# stm32f103c8.net
KiCad netlist of a schematic drawn in Altium Designer
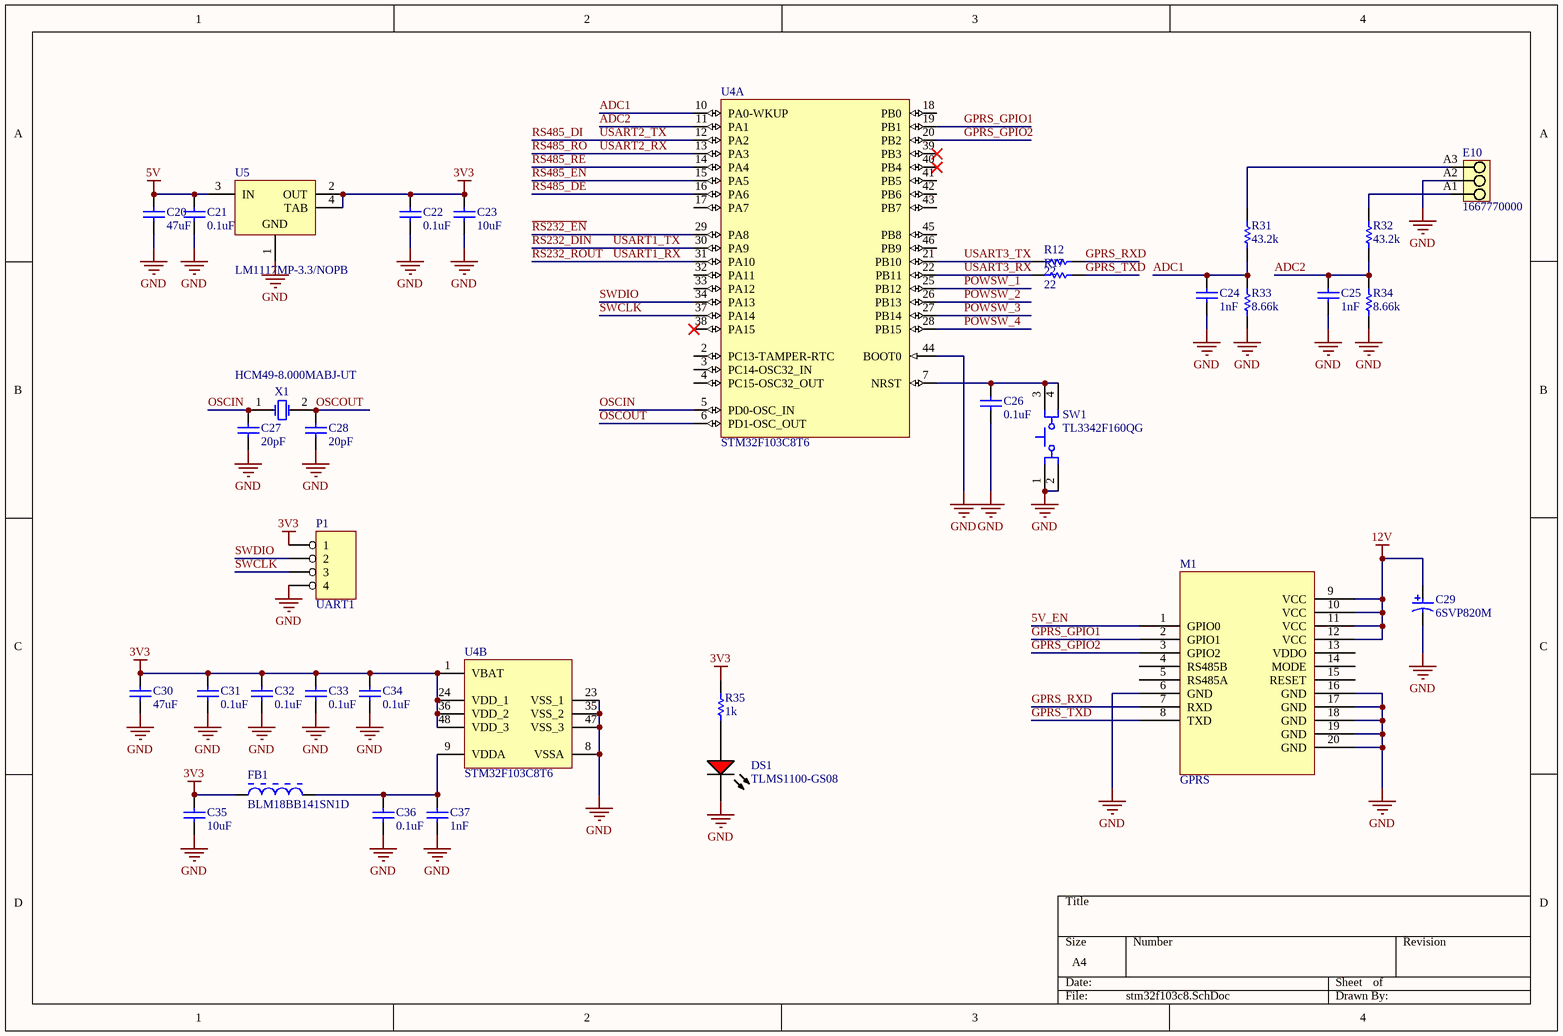
[diagram p0: stm32f103c8.SchDoc]

(export (version "E")
  (design (tool "Eeschema 10.0.6"))
  (components
    (comp (ref "C20")
      (value "47uF")
      (footprint "CAPC1206(3216)150_L")
      (description "1206 (3216 Metric) Chip Capacitor")
      (libsource (lib "IC0") (part "CAP_5_3"))
    )
    (comp (ref "C21")
      (value "0.1uF")
      (footprint "CAPC0603(1608)100_L")
      (description "0603 (1608 Metric) Chip Capacitor")
      (libsource (lib "IC0") (part "CAP_5"))
    )
    (comp (ref "C22")
      (value "0.1uF")
      (footprint "CAPC0603(1608)100_L")
      (description "0603 (1608 Metric) Chip Capacitor")
      (libsource (lib "IC0") (part "CAP_5"))
    )
    (comp (ref "C23")
      (value "10uF")
      (footprint "CAPC0805(2012)145_L")
      (description "0805 (2012 Metric) Chip Capacitor")
      (libsource (lib "IC0") (part "CAP_5_1"))
    )
    (comp (ref "C24")
      (value "1nF")
      (footprint "CAPC0603(1608)100_L")
      (description "0603 (1608 Metric) Chip Capacitor")
      (libsource (lib "IC0") (part "CAP_5"))
    )
    (comp (ref "C25")
      (value "1nF")
      (footprint "CAPC0603(1608)100_L")
      (description "0603 (1608 Metric) Chip Capacitor")
      (libsource (lib "IC0") (part "CAP_5"))
    )
    (comp (ref "C26")
      (value "0.1uF")
      (footprint "CAPC0603(1608)100_L")
      (description "0603 (1608 Metric) Chip Capacitor")
      (libsource (lib "IC0") (part "CAP_5"))
    )
    (comp (ref "C27")
      (value "20pF")
      (footprint "CAPC0603(1608)100_L")
      (description "0603 (1608 Metric) Chip Capacitor")
      (libsource (lib "IC0") (part "CAP_5"))
    )
    (comp (ref "C28")
      (value "20pF")
      (footprint "CAPC0603(1608)100_L")
      (description "0603 (1608 Metric) Chip Capacitor")
      (libsource (lib "IC0") (part "CAP_5"))
    )
    (comp (ref "C29")
      (value "6SVP820M")
      (footprint "PNSC-SVP-F12_L")
      (fields (field (name "TOLERANCE") "±20%") (field (name "MANUFACTURER") "Panasonic"))
      (libsource (lib "Altium Content Vault") (part "CAP-P-2"))
    )
    (comp (ref "C30")
      (value "47uF")
      (footprint "CAPC1206(3216)150_L")
      (description "1206 (3216 Metric) Chip Capacitor")
      (libsource (lib "IC0") (part "CAP_5_3"))
    )
    (comp (ref "C31")
      (value "0.1uF")
      (footprint "CAPC0603(1608)100_L")
      (description "0603 (1608 Metric) Chip Capacitor")
      (libsource (lib "IC0") (part "CAP_5"))
    )
    (comp (ref "C32")
      (value "0.1uF")
      (footprint "CAPC0603(1608)100_L")
      (description "0603 (1608 Metric) Chip Capacitor")
      (libsource (lib "IC0") (part "CAP_5"))
    )
    (comp (ref "C33")
      (value "0.1uF")
      (footprint "CAPC0603(1608)100_L")
      (description "0603 (1608 Metric) Chip Capacitor")
      (libsource (lib "IC0") (part "CAP_5"))
    )
    (comp (ref "C34")
      (value "0.1uF")
      (footprint "CAPC0603(1608)100_L")
      (description "0603 (1608 Metric) Chip Capacitor")
      (libsource (lib "IC0") (part "CAP_5"))
    )
    (comp (ref "C35")
      (value "10uF")
      (footprint "CAPC0603(1608)100_L")
      (description "0603 (1608 Metric) Chip Capacitor")
      (libsource (lib "IC0") (part "CAP_5"))
    )
    (comp (ref "C36")
      (value "0.1uF")
      (footprint "CAPC0603(1608)100_L")
      (description "0603 (1608 Metric) Chip Capacitor")
      (libsource (lib "IC0") (part "CAP_5"))
    )
    (comp (ref "C37")
      (value "1nF")
      (footprint "CAPC0603(1608)100_L")
      (description "0603 (1608 Metric) Chip Capacitor")
      (libsource (lib "IC0") (part "CAP_5"))
    )
    (comp (ref "DS1")
      (value "TLMS1100-GS08")
      (footprint "VISH-TLMX1100_V")
      (description "LED, RED, 2.1 V, -40 to 100 degC, 2-Pin SMD (0603), RoHS, Tape and Reel")
      (fields (field (name "TOLERANCE") "5%"))
      (libsource (lib "Altium Content Vault") (part "LED-RED-AK-2"))
    )
    (comp (ref "E10")
      (value "1667770000")
      (footprint "LM_3_5_90_03")
      (description "OMNIMATE Signal - series LM")
      (fields (field (name "MANUFACTURER") "Weidmueller"))
      (libsource (lib "Altium Content Vault") (part "Terminal_03_1x03"))
    )
    (comp (ref "FB1")
      (value "BLM18BB141SN1D")
      (footprint "MURA-BLM18-RF-H4-CHIP-2_V")
      (fields (field (name "MANUFACTURER") "Murata"))
      (libsource (lib "IC0") (part "MURA-FB-2"))
    )
    (comp (ref "M1") (value "GPRS") (footprint "GPRS") (libsource (lib "gprs") (part "GPRS_M")))
    (comp (ref "P1") (value "UART1") (footprint "header4") (libsource (lib "IC0") (part "HEADER 4")))
    (comp (ref "R12")
      (value "22")
      (footprint "RESC0603(1608)_L")
      (description "0603 (1608 Metric) Chip Resistor")
      (libsource (lib "PCB_Project1") (part "RES_3_1"))
    )
    (comp (ref "R17")
      (value "22")
      (footprint "RESC0603(1608)_L")
      (description "0603 (1608 Metric) Chip Resistor")
      (libsource (lib "PCB_Project1") (part "RES_3_1"))
    )
    (comp (ref "R31")
      (value "43.2k")
      (footprint "RESC0603(1608)_L")
      (description "0603 (1608 Metric) Chip Resistor")
      (libsource (lib "PCB_Project1") (part "RES_3_1"))
    )
    (comp (ref "R32")
      (value "43.2k")
      (footprint "RESC0603(1608)_L")
      (description "0603 (1608 Metric) Chip Resistor")
      (libsource (lib "PCB_Project1") (part "RES_3_1"))
    )
    (comp (ref "R33")
      (value "8.66k")
      (footprint "RESC0603(1608)_L")
      (description "0603 (1608 Metric) Chip Resistor")
      (libsource (lib "PCB_Project1") (part "RES_3_1"))
    )
    (comp (ref "R34")
      (value "8.66k")
      (footprint "RESC0603(1608)_L")
      (description "0603 (1608 Metric) Chip Resistor")
      (libsource (lib "PCB_Project1") (part "RES_3_1"))
    )
    (comp (ref "R35")
      (value "1k")
      (footprint "RESC0603(1608)_L")
      (description "0603 (1608 Metric) Chip Resistor")
      (libsource (lib "PCB_Project1") (part "RES_3_1"))
    )
    (comp (ref "SW1")
      (value "TL3342F160QG")
      (footprint "ESWI-TL3342F160QG_V")
      (description "Switch, Tactile, SPST-NO, 50 mA, 12 V, 4-Pin SMD, RoHS, Tape and Reel")
      (fields (field (name "TOLERANCE") "20%"))
      (libsource (lib "Altium Content Vault") (part "SW-SPST-NO-4"))
    )
    (comp (ref "U4")
      (value "STM32F103C8T6")
      (footprint "STM-LQFP48_L")
      (libsource (lib "Altium Content Vault") (part "MC-ARM-STM32F103X8_B-SQ48"))
    )
    (comp (ref "U5")
      (value "LM1117MP-3.3/NOPB")
      (footprint "DCY0004A_L")
      (description "800mA Low-Dropout Linear Regulator, 4-pin SOT-223, Pb-Free")
      (fields (field (name "MANUFACTURER") "Texas Instruments"))
      (libsource (lib "Altium Content Vault") (part "PM-REG-LM1086-SOT4"))
    )
    (comp (ref "X1")
      (value "HCM49-8.000MABJ-UT")
      (footprint "CFM-HCM49-2_V")
      (description "At-Cut Crystal Unit, 3.5 to 30 MHz, -40 to 85 degC, 2-Pin 11.4Ã—4.7Ã—4.3 mm SMD, RoHS, Reel")
      (fields (field (name "MANUFACTURER") "Citizen Finetech Miyota"))
      (libsource (lib "Altium Content Vault") (part "CFM-HCM49-2"))
    )
  )
  (nets
    (net (code "1") (name "/5V_EN") (class "Default")
      (node (ref "M1") (pin "1") (pinfunction "GPIO0_1") (pintype "passive"))
    )
    (net (code "2") (name "/ADC1") (class "Default")
      (node (ref "C24") (pin "2") (pinfunction "2_2") (pintype "passive"))
      (node (ref "R31") (pin "1") (pinfunction "1_1") (pintype "passive"))
      (node (ref "R33") (pin "2") (pinfunction "2_2") (pintype "passive"))
      (node (ref "U4") (pin "10") (pinfunction "PA0-WKUP_10") (pintype "bidirectional"))
    )
    (net (code "3") (name "/ADC2") (class "Default")
      (node (ref "C25") (pin "2") (pinfunction "2_2") (pintype "passive"))
      (node (ref "R32") (pin "1") (pinfunction "1_1") (pintype "passive"))
      (node (ref "R34") (pin "2") (pinfunction "2_2") (pintype "passive"))
      (node (ref "U4") (pin "11") (pinfunction "PA1_11") (pintype "bidirectional"))
    )
    (net (code "4") (name "/GPRS_GPIO1") (class "Default")
      (node (ref "M1") (pin "2") (pinfunction "GPIO1_2") (pintype "passive"))
      (node (ref "U4") (pin "19") (pinfunction "PB1_19") (pintype "bidirectional"))
    )
    (net (code "5") (name "/GPRS_GPIO2") (class "Default")
      (node (ref "M1") (pin "3") (pinfunction "GPIO2_3") (pintype "passive"))
      (node (ref "U4") (pin "20") (pinfunction "PB2_20") (pintype "bidirectional"))
    )
    (net (code "6") (name "/GPRS_RXD") (class "Default")
      (node (ref "M1") (pin "7") (pinfunction "RXD_7") (pintype "passive"))
      (node (ref "R12") (pin "1") (pinfunction "1_1") (pintype "passive"))
    )
    (net (code "7") (name "/GPRS_TXD") (class "Default")
      (node (ref "M1") (pin "8") (pinfunction "TXD_8") (pintype "passive"))
      (node (ref "R17") (pin "1") (pinfunction "1_1") (pintype "passive"))
    )
    (net (code "8") (name "/OSCIN") (class "Default")
      (node (ref "C27") (pin "2") (pinfunction "2_2") (pintype "passive"))
      (node (ref "U4") (pin "5") (pinfunction "PD0-OSC_IN_5") (pintype "bidirectional"))
      (node (ref "X1") (pin "1") (pinfunction "X1_1") (pintype "passive"))
    )
    (net (code "9") (name "/OSCOUT") (class "Default")
      (node (ref "C28") (pin "2") (pinfunction "2_2") (pintype "passive"))
      (node (ref "U4") (pin "6") (pinfunction "PD1-OSC_OUT_6") (pintype "bidirectional"))
      (node (ref "X1") (pin "2") (pinfunction "X2_2") (pintype "passive"))
    )
    (net (code "10") (name "/POWSW_1") (class "Default")
      (node (ref "U4") (pin "25") (pinfunction "PB12_25") (pintype "bidirectional"))
    )
    (net (code "11") (name "/POWSW_2") (class "Default")
      (node (ref "U4") (pin "26") (pinfunction "PB13_26") (pintype "bidirectional"))
    )
    (net (code "12") (name "/POWSW_3") (class "Default")
      (node (ref "U4") (pin "27") (pinfunction "PB14_27") (pintype "bidirectional"))
    )
    (net (code "13") (name "/POWSW_4") (class "Default")
      (node (ref "U4") (pin "28") (pinfunction "PB15_28") (pintype "bidirectional"))
    )
    (net (code "14") (name "/RS232_DIN") (class "Default")
      (node (ref "U4") (pin "30") (pinfunction "PA9_30") (pintype "bidirectional"))
    )
    (net (code "15") (name "/RS232_ROUT") (class "Default")
      (node (ref "U4") (pin "31") (pinfunction "PA10_31") (pintype "bidirectional"))
    )
    (net (code "16") (name "/RS485_DE") (class "Default")
      (node (ref "U4") (pin "16") (pinfunction "PA6_16") (pintype "bidirectional"))
    )
    (net (code "17") (name "/RS485_DI") (class "Default")
      (node (ref "U4") (pin "12") (pinfunction "PA2_12") (pintype "bidirectional"))
    )
    (net (code "18") (name "/RS485_RO") (class "Default")
      (node (ref "U4") (pin "13") (pinfunction "PA3_13") (pintype "bidirectional"))
    )
    (net (code "19") (name "/RS485_~{RE}") (class "Default")
      (node (ref "U4") (pin "14") (pinfunction "PA4_14") (pintype "bidirectional"))
    )
    (net (code "20") (name "/SWCLK") (class "Default")
      (node (ref "P1") (pin "3") (pinfunction "3_3") (pintype "passive"))
      (node (ref "U4") (pin "37") (pinfunction "PA14_37") (pintype "bidirectional"))
    )
    (net (code "21") (name "/SWDIO") (class "Default")
      (node (ref "P1") (pin "2") (pinfunction "2_2") (pintype "passive"))
      (node (ref "U4") (pin "34") (pinfunction "PA13_34") (pintype "bidirectional"))
    )
    (net (code "22") (name "/USART3_RX") (class "Default")
      (node (ref "R17") (pin "2") (pinfunction "2_2") (pintype "passive"))
      (node (ref "U4") (pin "22") (pinfunction "PB11_22") (pintype "bidirectional"))
    )
    (net (code "23") (name "/USART3_TX") (class "Default")
      (node (ref "R12") (pin "2") (pinfunction "2_2") (pintype "passive"))
      (node (ref "U4") (pin "21") (pinfunction "PB10_21") (pintype "bidirectional"))
    )
    (net (code "24") (name "/~{RS232_EN}") (class "Default")
      (node (ref "U4") (pin "29") (pinfunction "PA8_29") (pintype "bidirectional"))
    )
    (net (code "25") (name "/~{RS485_EN}") (class "Default")
      (node (ref "U4") (pin "15") (pinfunction "PA5_15") (pintype "bidirectional"))
    )
    (net (code "26") (name "3V3") (class "Default")
      (node (ref "C22") (pin "2") (pinfunction "2_2") (pintype "passive"))
      (node (ref "C23") (pin "2") (pinfunction "2_2") (pintype "passive"))
      (node (ref "C30") (pin "2") (pinfunction "2_2") (pintype "passive"))
      (node (ref "C31") (pin "2") (pinfunction "2_2") (pintype "passive"))
      (node (ref "C32") (pin "2") (pinfunction "2_2") (pintype "passive"))
      (node (ref "C33") (pin "2") (pinfunction "2_2") (pintype "passive"))
      (node (ref "C34") (pin "2") (pinfunction "2_2") (pintype "passive"))
      (node (ref "C35") (pin "2") (pinfunction "2_2") (pintype "passive"))
      (node (ref "FB1") (pin "1") (pinfunction "1_1") (pintype "passive"))
      (node (ref "P1") (pin "1") (pinfunction "1_1") (pintype "passive"))
      (node (ref "R35") (pin "2") (pinfunction "2_2") (pintype "passive"))
      (node (ref "U4") (pin "1") (pinfunction "VBAT_1") (pintype "power_in"))
      (node (ref "U4") (pin "24") (pinfunction "VDD_1_24") (pintype "power_in"))
      (node (ref "U4") (pin "36") (pinfunction "VDD_2_36") (pintype "power_in"))
      (node (ref "U4") (pin "48") (pinfunction "VDD_3_48") (pintype "power_in"))
      (node (ref "U5") (pin "2") (pinfunction "OUT_2") (pintype "power_in"))
      (node (ref "U5") (pin "4") (pinfunction "TAB_4") (pintype "power_in"))
    )
    (net (code "27") (name "5V") (class "Default")
      (node (ref "C20") (pin "2") (pinfunction "2_2") (pintype "passive"))
      (node (ref "C21") (pin "2") (pinfunction "2_2") (pintype "passive"))
      (node (ref "U5") (pin "3") (pinfunction "IN_3") (pintype "power_in"))
    )
    (net (code "28") (name "12V") (class "Default")
      (node (ref "C29") (pin "1") (pinfunction "1_1") (pintype "passive"))
      (node (ref "M1") (pin "10") (pinfunction "VCC_10") (pintype "passive"))
      (node (ref "M1") (pin "11") (pinfunction "VCC_11") (pintype "passive"))
      (node (ref "M1") (pin "12") (pinfunction "VCC_12") (pintype "passive"))
      (node (ref "M1") (pin "9") (pinfunction "VCC_9") (pintype "passive"))
    )
    (net (code "29") (name "GND") (class "Default")
      (node (ref "C20") (pin "1") (pinfunction "1_1") (pintype "passive"))
      (node (ref "C21") (pin "1") (pinfunction "1_1") (pintype "passive"))
      (node (ref "C22") (pin "1") (pinfunction "1_1") (pintype "passive"))
      (node (ref "C23") (pin "1") (pinfunction "1_1") (pintype "passive"))
      (node (ref "C24") (pin "1") (pinfunction "1_1") (pintype "passive"))
      (node (ref "C25") (pin "1") (pinfunction "1_1") (pintype "passive"))
      (node (ref "C26") (pin "1") (pinfunction "1_1") (pintype "passive"))
      (node (ref "C27") (pin "1") (pinfunction "1_1") (pintype "passive"))
      (node (ref "C28") (pin "1") (pinfunction "1_1") (pintype "passive"))
      (node (ref "C29") (pin "2") (pinfunction "2_2") (pintype "passive"))
      (node (ref "C30") (pin "1") (pinfunction "1_1") (pintype "passive"))
      (node (ref "C31") (pin "1") (pinfunction "1_1") (pintype "passive"))
      (node (ref "C32") (pin "1") (pinfunction "1_1") (pintype "passive"))
      (node (ref "C33") (pin "1") (pinfunction "1_1") (pintype "passive"))
      (node (ref "C34") (pin "1") (pinfunction "1_1") (pintype "passive"))
      (node (ref "C35") (pin "1") (pinfunction "1_1") (pintype "passive"))
      (node (ref "C36") (pin "1") (pinfunction "1_1") (pintype "passive"))
      (node (ref "C37") (pin "1") (pinfunction "1_1") (pintype "passive"))
      (node (ref "DS1") (pin "2") (pinfunction "K_2") (pintype "passive"))
      (node (ref "E10") (pin "A2") (pinfunction "A2_A2") (pintype "passive"))
      (node (ref "M1") (pin "16") (pinfunction "GND_16") (pintype "passive"))
      (node (ref "M1") (pin "17") (pinfunction "GND_17") (pintype "passive"))
      (node (ref "M1") (pin "18") (pinfunction "GND_18") (pintype "passive"))
      (node (ref "M1") (pin "19") (pinfunction "GND_19") (pintype "passive"))
      (node (ref "M1") (pin "20") (pinfunction "GND_20") (pintype "passive"))
      (node (ref "M1") (pin "6") (pinfunction "GND_6") (pintype "passive"))
      (node (ref "P1") (pin "4") (pinfunction "4_4") (pintype "passive"))
      (node (ref "R33") (pin "1") (pinfunction "1_1") (pintype "passive"))
      (node (ref "R34") (pin "1") (pinfunction "1_1") (pintype "passive"))
      (node (ref "SW1") (pin "1") (pinfunction "1_1") (pintype "passive"))
      (node (ref "SW1") (pin "2") (pinfunction "2_2") (pintype "passive"))
      (node (ref "U4") (pin "23") (pinfunction "VSS_1_23") (pintype "power_in"))
      (node (ref "U4") (pin "35") (pinfunction "VSS_2_35") (pintype "power_in"))
      (node (ref "U4") (pin "44") (pinfunction "BOOT0_44") (pintype "input"))
      (node (ref "U4") (pin "47") (pinfunction "VSS_3_47") (pintype "power_in"))
      (node (ref "U4") (pin "8") (pinfunction "VSSA_8") (pintype "power_in"))
      (node (ref "U5") (pin "1") (pinfunction "GND_1") (pintype "power_in"))
    )
    (net (code "30") (name "Net-(DS1-A)") (class "Default")
      (node (ref "DS1") (pin "1") (pinfunction "A_1") (pintype "passive"))
      (node (ref "R35") (pin "1") (pinfunction "1_1") (pintype "passive"))
    )
    (net (code "31") (name "Net-(E10-PadA1)") (class "Default")
      (node (ref "E10") (pin "A1") (pinfunction "A1_A1") (pintype "passive"))
      (node (ref "R32") (pin "2") (pinfunction "2_2") (pintype "passive"))
    )
    (net (code "32") (name "Net-(E10-PadA3)") (class "Default")
      (node (ref "E10") (pin "A3") (pinfunction "A3_A3") (pintype "passive"))
      (node (ref "R31") (pin "2") (pinfunction "2_2") (pintype "passive"))
    )
    (net (code "33") (name "Net-(U4A-NRST)") (class "Default")
      (node (ref "C26") (pin "2") (pinfunction "2_2") (pintype "passive"))
      (node (ref "SW1") (pin "3") (pinfunction "3_3") (pintype "passive"))
      (node (ref "SW1") (pin "4") (pinfunction "4_4") (pintype "passive"))
      (node (ref "U4") (pin "7") (pinfunction "NRST_7") (pintype "bidirectional"))
    )
    (net (code "34") (name "Net-(U4B-VDDA)") (class "Default")
      (node (ref "C36") (pin "2") (pinfunction "2_2") (pintype "passive"))
      (node (ref "C37") (pin "2") (pinfunction "2_2") (pintype "passive"))
      (node (ref "FB1") (pin "2") (pinfunction "2_2") (pintype "passive"))
      (node (ref "U4") (pin "9") (pinfunction "VDDA_9") (pintype "power_in"))
    )
    (net (code "35") (name "unconnected-(M1-MODE-Pad14)") (class "Default")
      (node (ref "M1") (pin "14") (pinfunction "MODE_14") (pintype "passive"))
    )
    (net (code "36") (name "unconnected-(M1-RESET-Pad15)") (class "Default")
      (node (ref "M1") (pin "15") (pinfunction "RESET_15") (pintype "passive"))
    )
    (net (code "37") (name "unconnected-(M1-RS485A-Pad5)") (class "Default")
      (node (ref "M1") (pin "5") (pinfunction "RS485A_5") (pintype "passive"))
    )
    (net (code "38") (name "unconnected-(M1-RS485B-Pad4)") (class "Default")
      (node (ref "M1") (pin "4") (pinfunction "RS485B_4") (pintype "passive"))
    )
    (net (code "39") (name "unconnected-(M1-VDDO-Pad13)") (class "Default")
      (node (ref "M1") (pin "13") (pinfunction "VDDO_13") (pintype "passive"))
    )
    (net (code "40") (name "unconnected-(U4A-PA7-Pad17)") (class "Default")
      (node (ref "U4") (pin "17") (pinfunction "PA7_17") (pintype "bidirectional"))
    )
    (net (code "41") (name "unconnected-(U4A-PA11-Pad32)") (class "Default")
      (node (ref "U4") (pin "32") (pinfunction "PA11_32") (pintype "bidirectional"))
    )
    (net (code "42") (name "unconnected-(U4A-PA12-Pad33)") (class "Default")
      (node (ref "U4") (pin "33") (pinfunction "PA12_33") (pintype "bidirectional"))
    )
    (net (code "43") (name "unconnected-(U4A-PA15-Pad38)") (class "Default")
      (node (ref "U4") (pin "38") (pinfunction "PA15_38") (pintype "bidirectional+no_connect"))
    )
    (net (code "44") (name "unconnected-(U4A-PB0-Pad18)") (class "Default")
      (node (ref "U4") (pin "18") (pinfunction "PB0_18") (pintype "bidirectional"))
    )
    (net (code "45") (name "unconnected-(U4A-PB3-Pad39)") (class "Default")
      (node (ref "U4") (pin "39") (pinfunction "PB3_39") (pintype "bidirectional+no_connect"))
    )
    (net (code "46") (name "unconnected-(U4A-PB4-Pad40)") (class "Default")
      (node (ref "U4") (pin "40") (pinfunction "PB4_40") (pintype "bidirectional+no_connect"))
    )
    (net (code "47") (name "unconnected-(U4A-PB5-Pad41)") (class "Default")
      (node (ref "U4") (pin "41") (pinfunction "PB5_41") (pintype "bidirectional"))
    )
    (net (code "48") (name "unconnected-(U4A-PB6-Pad42)") (class "Default")
      (node (ref "U4") (pin "42") (pinfunction "PB6_42") (pintype "bidirectional"))
    )
    (net (code "49") (name "unconnected-(U4A-PB7-Pad43)") (class "Default")
      (node (ref "U4") (pin "43") (pinfunction "PB7_43") (pintype "bidirectional"))
    )
    (net (code "50") (name "unconnected-(U4A-PB8-Pad45)") (class "Default")
      (node (ref "U4") (pin "45") (pinfunction "PB8_45") (pintype "bidirectional"))
    )
    (net (code "51") (name "unconnected-(U4A-PB9-Pad46)") (class "Default")
      (node (ref "U4") (pin "46") (pinfunction "PB9_46") (pintype "bidirectional"))
    )
    (net (code "52") (name "unconnected-(U4A-PC13-TAMPER-RTC-Pad2)") (class "Default")
      (node (ref "U4") (pin "2") (pinfunction "PC13-TAMPER-RTC_2") (pintype "bidirectional"))
    )
    (net (code "53") (name "unconnected-(U4A-PC14-OSC32_IN-Pad3)") (class "Default")
      (node (ref "U4") (pin "3") (pinfunction "PC14-OSC32_IN_3") (pintype "bidirectional"))
    )
    (net (code "54") (name "unconnected-(U4A-PC15-OSC32_OUT-Pad4)") (class "Default")
      (node (ref "U4") (pin "4") (pinfunction "PC15-OSC32_OUT_4") (pintype "bidirectional"))
    )
  )
)
